# main.net
KiCad netlist of a schematic drawn in Altium Designer
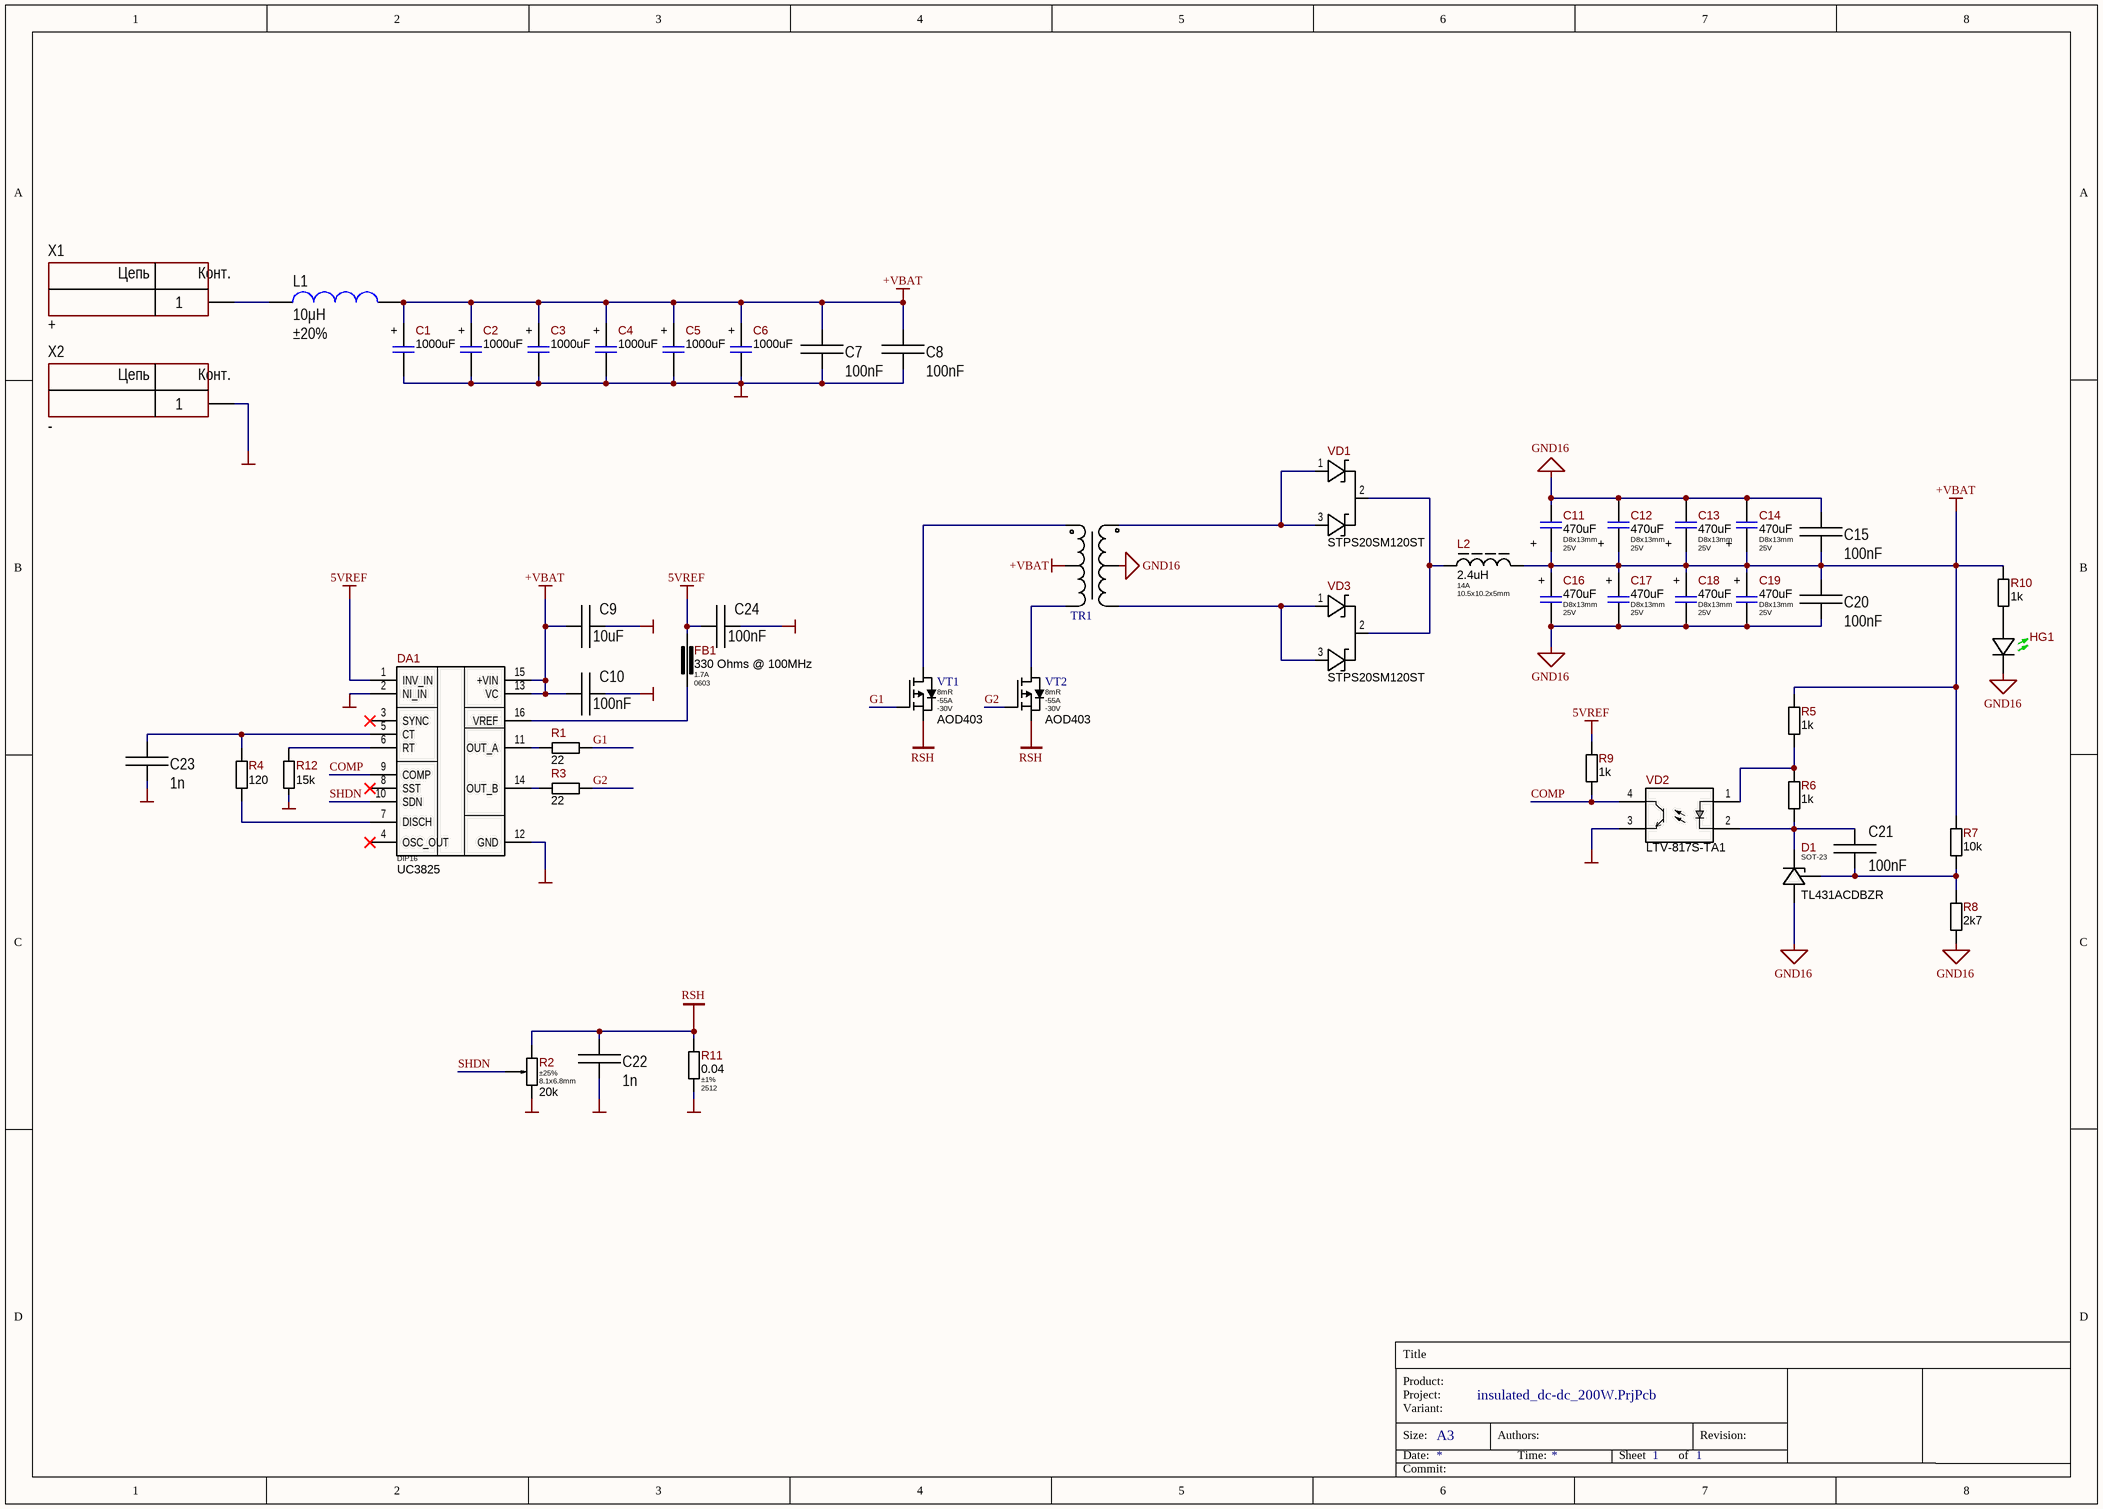
[diagram p0: main.SchDoc]

(export (version "E")
  (design (tool "Eeschema 10.0.6"))
  (components
    (comp (ref "C1")
      (value "1000uF")
      (footprint "CAP-AE-PTH-100D05x200H20")
      (description "1000uF 25V ±20% Aluminum Electrolytic Capacitors Radial, 2000 Hrs @ 105°C, 740mA Ripple Current")
      (fields (field (name "VOLTAGE") "25V") (field (name "PART NUMBER") "ESH108M025AH4AA"))
      (libsource (lib "capacitors") (part "ESH108M025AH4AA"))
    )
    (comp (ref "C2")
      (value "1000uF")
      (footprint "CAP-AE-PTH-100D05x200H20")
      (description "1000uF 25V ±20% Aluminum Electrolytic Capacitors Radial, 2000 Hrs @ 105°C, 740mA Ripple Current")
      (fields (field (name "VOLTAGE") "25V") (field (name "PART NUMBER") "ESH108M025AH4AA"))
      (libsource (lib "capacitors") (part "ESH108M025AH4AA"))
    )
    (comp (ref "C3")
      (value "1000uF")
      (footprint "CAP-AE-PTH-100D05x200H20")
      (description "1000uF 25V ±20% Aluminum Electrolytic Capacitors Radial, 2000 Hrs @ 105°C, 740mA Ripple Current")
      (fields (field (name "VOLTAGE") "25V") (field (name "PART NUMBER") "ESH108M025AH4AA"))
      (libsource (lib "capacitors") (part "ESH108M025AH4AA"))
    )
    (comp (ref "C4")
      (value "1000uF")
      (footprint "CAP-AE-PTH-100D05x200H20")
      (description "1000uF 25V ±20% Aluminum Electrolytic Capacitors Radial, 2000 Hrs @ 105°C, 740mA Ripple Current")
      (fields (field (name "VOLTAGE") "25V") (field (name "PART NUMBER") "ESH108M025AH4AA"))
      (libsource (lib "capacitors") (part "ESH108M025AH4AA"))
    )
    (comp (ref "C5")
      (value "1000uF")
      (footprint "CAP-AE-PTH-100D05x200H20")
      (description "1000uF 25V ±20% Aluminum Electrolytic Capacitors Radial, 2000 Hrs @ 105°C, 740mA Ripple Current")
      (fields (field (name "VOLTAGE") "25V") (field (name "PART NUMBER") "ESH108M025AH4AA"))
      (libsource (lib "capacitors") (part "ESH108M025AH4AA"))
    )
    (comp (ref "C6")
      (value "1000uF")
      (footprint "CAP-AE-PTH-100D05x200H20")
      (description "1000uF 25V ±20% Aluminum Electrolytic Capacitors Radial, 2000 Hrs @ 105°C, 740mA Ripple Current")
      (fields (field (name "VOLTAGE") "25V") (field (name "PART NUMBER") "ESH108M025AH4AA"))
      (libsource (lib "capacitors") (part "ESH108M025AH4AA"))
    )
    (comp (ref "C7")
      (value "100nF")
      (footprint "CAP: MKS2 (W=2.50MM)")
      (fields
        (field (name "MANUFACTURER") "Epcos")
        (field (name "PARTNUMBER") "B32774D4106K000")
        (field (name "VALUEMANUFACTURERPARTNUMBER") "Film capacitor, 100nF, 450VDC, ±10%, 10.9mOhm, 31.5x15 mm, -40...+105°C")
      )
      (libsource (lib "capacitor") (part "Film"))
    )
    (comp (ref "C8")
      (value "100nF")
      (footprint "CAP: MKS2 (W=2.50MM)")
      (fields
        (field (name "MANUFACTURER") "Epcos")
        (field (name "PARTNUMBER") "B32774D4106K000")
        (field (name "VALUEMANUFACTURERPARTNUMBER") "Film capacitor, 100nF, 450VDC, ±10%, 10.9mOhm, 31.5x15 mm, -40...+105°C")
      )
      (libsource (lib "capacitor") (part "Film"))
    )
    (comp (ref "C9")
      (value "10uF")
      (footprint "CAP: MKS2 (W=2.50MM)")
      (fields
        (field (name "MANUFACTURER") "Epcos")
        (field (name "PARTNUMBER") "B32774D4106K000")
        (field (name "VALUEMANUFACTURERPARTNUMBER") "Film capacitor, 10uF, 450VDC, ±10%, 10.9mOhm, 31.5x15 mm, -40...+105°C")
      )
      (libsource (lib "capacitor") (part "Film"))
    )
    (comp (ref "C10")
      (value "100nF")
      (footprint "CAP: MKS2 (W=2.50MM)")
      (fields
        (field (name "MANUFACTURER") "Epcos")
        (field (name "PARTNUMBER") "B32774D4106K000")
        (field (name "VALUEMANUFACTURERPARTNUMBER") "Film capacitor, 100nF, 450VDC, ±10%, 10.9mOhm, 31.5x15 mm, -40...+105°C")
      )
      (libsource (lib "capacitor") (part "Film"))
    )
    (comp (ref "C11")
      (value "470uF")
      (footprint "CAP-AE-PTH-80D05x130H15")
      (fields
        (field (name "PACKAGE") "D8x13mm")
        (field (name "VOLTAGE") "25V")
        (field (name "PART NUMBER") "KS-025V471MF130")
        (field (name "MANUFACTURER") "Koshin")
        (field (name "TOLERANCE") "±20%")
      )
      (libsource (lib "capacitors") (part "KS-025V471MF130"))
    )
    (comp (ref "C12")
      (value "470uF")
      (footprint "CAP-AE-PTH-80D05x130H15")
      (fields
        (field (name "PACKAGE") "D8x13mm")
        (field (name "VOLTAGE") "25V")
        (field (name "PART NUMBER") "KS-025V471MF130")
        (field (name "MANUFACTURER") "Koshin")
        (field (name "TOLERANCE") "±20%")
      )
      (libsource (lib "capacitors") (part "KS-025V471MF130"))
    )
    (comp (ref "C13")
      (value "470uF")
      (footprint "CAP-AE-PTH-80D05x130H15")
      (fields
        (field (name "PACKAGE") "D8x13mm")
        (field (name "VOLTAGE") "25V")
        (field (name "PART NUMBER") "KS-025V471MF130")
        (field (name "MANUFACTURER") "Koshin")
        (field (name "TOLERANCE") "±20%")
      )
      (libsource (lib "capacitors") (part "KS-025V471MF130"))
    )
    (comp (ref "C14")
      (value "470uF")
      (footprint "CAP-AE-PTH-80D05x130H15")
      (fields
        (field (name "PACKAGE") "D8x13mm")
        (field (name "VOLTAGE") "25V")
        (field (name "PART NUMBER") "KS-025V471MF130")
        (field (name "MANUFACTURER") "Koshin")
        (field (name "TOLERANCE") "±20%")
      )
      (libsource (lib "capacitors") (part "KS-025V471MF130"))
    )
    (comp (ref "C15")
      (value "100nF")
      (footprint "CAP: MKS2 (W=2.50MM)")
      (fields
        (field (name "MANUFACTURER") "Epcos")
        (field (name "PARTNUMBER") "B32774D4106K000")
        (field (name "VALUEMANUFACTURERPARTNUMBER") "Film capacitor, 100nF, 450VDC, ±10%, 10.9mOhm, 31.5x15 mm, -40...+105°C")
      )
      (libsource (lib "capacitor") (part "Film"))
    )
    (comp (ref "C16")
      (value "470uF")
      (footprint "CAP-AE-PTH-80D05x130H15")
      (fields
        (field (name "PACKAGE") "D8x13mm")
        (field (name "VOLTAGE") "25V")
        (field (name "PART NUMBER") "KS-025V471MF130")
        (field (name "MANUFACTURER") "Koshin")
        (field (name "TOLERANCE") "±20%")
      )
      (libsource (lib "capacitors") (part "KS-025V471MF130"))
    )
    (comp (ref "C17")
      (value "470uF")
      (footprint "CAP-AE-PTH-80D05x130H15")
      (fields
        (field (name "PACKAGE") "D8x13mm")
        (field (name "VOLTAGE") "25V")
        (field (name "PART NUMBER") "KS-025V471MF130")
        (field (name "MANUFACTURER") "Koshin")
        (field (name "TOLERANCE") "±20%")
      )
      (libsource (lib "capacitors") (part "KS-025V471MF130"))
    )
    (comp (ref "C18")
      (value "470uF")
      (footprint "CAP-AE-PTH-80D05x130H15")
      (fields
        (field (name "PACKAGE") "D8x13mm")
        (field (name "VOLTAGE") "25V")
        (field (name "PART NUMBER") "KS-025V471MF130")
        (field (name "MANUFACTURER") "Koshin")
        (field (name "TOLERANCE") "±20%")
      )
      (libsource (lib "capacitors") (part "KS-025V471MF130"))
    )
    (comp (ref "C19")
      (value "470uF")
      (footprint "CAP-AE-PTH-80D05x130H15")
      (fields
        (field (name "PACKAGE") "D8x13mm")
        (field (name "VOLTAGE") "25V")
        (field (name "PART NUMBER") "KS-025V471MF130")
        (field (name "MANUFACTURER") "Koshin")
        (field (name "TOLERANCE") "±20%")
      )
      (libsource (lib "capacitors") (part "KS-025V471MF130"))
    )
    (comp (ref "C20")
      (value "100nF")
      (footprint "CAP: MKS2 (W=2.50MM)")
      (fields
        (field (name "MANUFACTURER") "Epcos")
        (field (name "PARTNUMBER") "B32774D4106K000")
        (field (name "VALUEMANUFACTURERPARTNUMBER") "Film capacitor, 100nF, 450VDC, ±10%, 10.9mOhm, 31.5x15 mm, -40...+105°C")
      )
      (libsource (lib "capacitor") (part "Film"))
    )
    (comp (ref "C21")
      (value "100nF")
      (footprint "CAP: MKS2 (W=2.50MM)")
      (fields
        (field (name "MANUFACTURER") "Epcos")
        (field (name "PARTNUMBER") "B32774D4106K000")
        (field (name "VALUEMANUFACTURERPARTNUMBER") "Film capacitor, 100nF, 450VDC, ±10%, 10.9mOhm, 31.5x15 mm, -40...+105°C")
      )
      (libsource (lib "capacitor") (part "Film"))
    )
    (comp (ref "C22")
      (value "1n")
      (footprint "CAP: MKS2 (W=2.50MM)")
      (fields
        (field (name "MANUFACTURER") "Epcos")
        (field (name "PARTNUMBER") "B32774D4106K000")
        (field (name "VALUEMANUFACTURERPARTNUMBER") "Film capacitor, 1n, 450VDC, ±10%, 10.9mOhm, 31.5x15 mm, -40...+105°C")
      )
      (libsource (lib "capacitor") (part "Film"))
    )
    (comp (ref "C23")
      (value "1n")
      (footprint "CAP: MKS2 (W=2.50MM)")
      (fields
        (field (name "MANUFACTURER") "Epcos")
        (field (name "PARTNUMBER") "B32774D4106K000")
        (field (name "VALUEMANUFACTURERPARTNUMBER") "Film capacitor, 1n, 450VDC, ±10%, 10.9mOhm, 31.5x15 mm, -40...+105°C")
      )
      (libsource (lib "capacitor") (part "Film"))
    )
    (comp (ref "C24")
      (value "100nF")
      (footprint "CAP: MKS2 (W=2.50MM)")
      (fields
        (field (name "MANUFACTURER") "Epcos")
        (field (name "PARTNUMBER") "B32774D4106K000")
        (field (name "VALUEMANUFACTURERPARTNUMBER") "Film capacitor, 100nF, 450VDC, ±10%, 10.9mOhm, 31.5x15 mm, -40...+105°C")
      )
      (libsource (lib "capacitor") (part "Film"))
    )
    (comp (ref "D1")
      (value "TL431ACDBZR")
      (footprint "SOT-23_MED")
      (description "Adjustable Precision Shunt Regulator, Accuracy 1%,  SOT-23-3")
      (fields
        (field (name "PACKAGE") "SOT-23")
        (field (name "PART NUMBER") "TL431ACDBZR")
        (field (name "MANUFACTURER") "Texas Instruments")
      )
      (libsource (lib "ic") (part "TL431ACDBZR"))
    )
    (comp (ref "DA1")
      (value "UC3525")
      (footprint "DIP16")
      (fields
        (field (name "MANUFACTURER") "Texas")
        (field (name "PACKAGE") "DIP16")
        (field (name "PART NUMBER") "UC3825")
      )
      (libsource (lib "vitech_lib") (part "UC3525"))
    )
    (comp (ref "FB1")
      (value "330 Ohms @ 100MHz")
      (footprint "BLM18-Series_H80T15")
      (description "330 Ohms @ 100 MHz Power Line Ferrite Bead 0603, 1.7A 80mOhm")
      (fields
        (field (name "CURRENT") "1.7A")
        (field (name "PACKAGE") "0603")
        (field (name "PART NUMBER") "BLM18KG331SH1D")
        (field (name "TOLERANCE") "±25%")
      )
      (libsource (lib "inductors") (part "BLM18KG331SH1D"))
    )
    (comp (ref "HG1")
      (value "LTST-C171GKT")
      (footprint "LTST-C171GKT")
      (description "Low Power LED, Green 565nm, Clear, SMD 0805, Vf 2.1V - 2.6V, 5 ~ 12mcd @ 20 mA, 130°")
      (fields (field (name "MANUFACTURER") "Lite-On Optoelectronics"))
      (libsource (lib "opto") (part "LTST-C171GKT"))
    )
    (comp (ref "L1")
      (value "10μH")
      (footprint "IND: R22.9/14/7.62 (H)")
      (fields
        (field (name "MANUFACTURER") "Magnetics")
        (field (name "PARTNUMBER") "0077310A7")
        (field (name "VALUEMANUFACTURERPARTNUMBER") "Fixed inductor, 10μH, ±20%, R22.9/14/7.62, Kool Mu, µ=125, 90 нГн/витков2")
        (field (name "TOLERANCE") "±20%")
      )
      (libsource (lib "inductor") (part "Inductor_R22.9/14/7.62"))
    )
    (comp (ref "L2")
      (value "2.4uH")
      (footprint "744325240")
      (description "2.4uH Shielded Wirewound Inductor 14A 4.75mOhm Max, 10.5x10.2mm, Height 5mm Max")
      (fields
        (field (name "CURRENT") "14A")
        (field (name "PACKAGE") "10.5x10.2x5mm")
        (field (name "PART NUMBER") "744325240")
        (field (name "TOLERANCE") "±20%")
      )
      (libsource (lib "inductors") (part "744325240"))
    )
    (comp (ref "R1")
      (value "22")
      (footprint "R_ANY_CHIP_0805_MED")
      (description "22 Ohms ±5%, 1/8W 0805 Thick Film Resistor")
      (fields (field (name "TOLERANCE") "±5%") (field (name "PART NUMBER") "RC0805JR-0722RL"))
      (libsource (lib "resistors") (part "RC0805JR-0722RL"))
    )
    (comp (ref "R2")
      (value "20k")
      (footprint "3306F-1-xxx")
      (description "20 kOhms ±25%, 0.2W, PTH Trimmer Potentiometer, Cermet, Turn Top Adjustment")
      (fields
        (field (name "TOLERANCE") "±25%")
        (field (name "PACKAGE") "8.1x6.8mm")
        (field (name "PART NUMBER") "3306F-1-203")
        (field (name "MANUFACTURER") "Bourns")
      )
      (libsource (lib "resistors") (part "3306F-1-203"))
    )
    (comp (ref "R3")
      (value "22")
      (footprint "R_ANY_CHIP_0805_MED")
      (description "22 Ohms ±5%, 1/8W 0805 Thick Film Resistor")
      (fields (field (name "TOLERANCE") "±5%") (field (name "PART NUMBER") "RC0805JR-0722RL"))
      (libsource (lib "resistors") (part "RC0805JR-0722RL"))
    )
    (comp (ref "R4")
      (value "120")
      (footprint "R_ANY_CHIP_0805_MED")
      (description "22 Ohms ±5%, 1/8W 0805 Thick Film Resistor")
      (fields (field (name "TOLERANCE") "±5%") (field (name "PART NUMBER") "RC0805JR-0722RL"))
      (libsource (lib "resistors") (part "RC0805JR-0722RL"))
    )
    (comp (ref "R5")
      (value "1k")
      (footprint "R_ANY_CHIP_0805_MED")
      (description "22 Ohms ±5%, 1/8W 0805 Thick Film Resistor")
      (fields (field (name "TOLERANCE") "±5%") (field (name "PART NUMBER") "RC0805JR-0722RL"))
      (libsource (lib "resistors") (part "RC0805JR-0722RL"))
    )
    (comp (ref "R6")
      (value "1k")
      (footprint "R_ANY_CHIP_0805_MED")
      (description "22 Ohms ±5%, 1/8W 0805 Thick Film Resistor")
      (fields (field (name "TOLERANCE") "±5%") (field (name "PART NUMBER") "RC0805JR-0722RL"))
      (libsource (lib "resistors") (part "RC0805JR-0722RL"))
    )
    (comp (ref "R7")
      (value "10k")
      (footprint "R_ANY_CHIP_0805_MED")
      (description "22 Ohms ±5%, 1/8W 0805 Thick Film Resistor")
      (fields (field (name "TOLERANCE") "±5%") (field (name "PART NUMBER") "RC0805JR-0722RL"))
      (libsource (lib "resistors") (part "RC0805JR-0722RL"))
    )
    (comp (ref "R8")
      (value "2k7")
      (footprint "R_ANY_CHIP_0805_MED")
      (description "22 Ohms ±5%, 1/8W 0805 Thick Film Resistor")
      (fields (field (name "TOLERANCE") "±5%") (field (name "PART NUMBER") "RC0805JR-0722RL"))
      (libsource (lib "resistors") (part "RC0805JR-0722RL"))
    )
    (comp (ref "R9")
      (value "1k")
      (footprint "R_ANY_CHIP_0805_MED")
      (description "22 Ohms ±5%, 1/8W 0805 Thick Film Resistor")
      (fields (field (name "TOLERANCE") "±5%") (field (name "PART NUMBER") "RC0805JR-0722RL"))
      (libsource (lib "resistors") (part "RC0805JR-0722RL"))
    )
    (comp (ref "R10")
      (value "1k")
      (footprint "R_ANY_CHIP_0805_MED")
      (description "22 Ohms ±5%, 1/8W 0805 Thick Film Resistor")
      (fields (field (name "TOLERANCE") "±5%") (field (name "PART NUMBER") "RC0805JR-0722RL"))
      (libsource (lib "resistors") (part "RC0805JR-0722RL"))
    )
    (comp (ref "R11")
      (value "0.04")
      (footprint "HoLLR2512-Series")
      (description "40mOhm ±1%, 2W Surface Mount 77.5A ±50ppm 2512 Encapsulated Metal Alloy Current Sense Resistors")
      (fields
        (field (name "TOLERANCE") "±1%")
        (field (name "PACKAGE") "2512")
        (field (name "PART NUMBER") "HoLLR2512-2W-40mR-1%")
        (field (name "MANUFACTURER") "Milliohm")
      )
      (libsource (lib "resistors") (part "HoLLR2512-2W-40mR-1%"))
    )
    (comp (ref "R12")
      (value "15k")
      (footprint "R_ANY_CHIP_0805_MED")
      (description "22 Ohms ±5%, 1/8W 0805 Thick Film Resistor")
      (fields (field (name "TOLERANCE") "±5%") (field (name "PART NUMBER") "RC0805JR-0722RL"))
      (libsource (lib "resistors") (part "RC0805JR-0722RL"))
    )
    (comp (ref "TR1")
      (value "TR")
      (footprint "TR: R32.8/20.1/10.7 (L) - MidPoint - 2")
      (fields
        (field (name "MANUFACTURER") "Handmade")
        (field (name "PART NUMBER") "RLB0914-3R3ML-ND")
        (field (name "TOLERANCE") "±20%")
      )
      (libsource (lib "vitech_lib") (part "Toroidal Transformator Midpoint_1"))
    )
    (comp (ref "VD1")
      (value "DIODE SCHOTTKY")
      (footprint "TO220(H)")
      (description "Diode Schottky Array 1 Pair Common Cathode, 120V 20A, TO-220")
      (fields
        (field (name "VOLTAGE") "120V")
        (field (name "MANUFACTURER") "STMicroelectronics")
        (field (name "PART NUMBER") "STPS20SM120ST")
      )
      (libsource (lib "vitech_lib") (part "DIODE SCHOTTKY"))
    )
    (comp (ref "VD2")
      (value "LTV-817S-TA1")
      (footprint "LTV-817S-TA1_REC")
      (description "1-Channel Photocoupler, 5kV, SSOP-4")
      (fields
        (field (name "PART NUMBER") "LTV-817S-TA1")
        (field (name "MANUFACTURER") "Lite-On Optoelectronics")
      )
      (libsource (lib "opto") (part "LTV-817S-TA1"))
    )
    (comp (ref "VD3")
      (value "DIODE SCHOTTKY")
      (footprint "TO220(H)")
      (description "Diode Schottky Array 1 Pair Common Cathode, 120V 20A, TO-220")
      (fields
        (field (name "VOLTAGE") "120V")
        (field (name "MANUFACTURER") "STMicroelectronics")
        (field (name "PART NUMBER") "STPS20SM120ST")
      )
      (libsource (lib "vitech_lib") (part "DIODE SCHOTTKY"))
    )
    (comp (ref "VT1")
      (value "AOD403")
      (footprint "TO220(H)")
      (description "P-MOSFET; полевой; -30В; -55А; 45Вт; TO252")
      (fields
        (field (name "RDS") "8mR")
        (field (name "ID") "-55А")
        (field (name "VDS") "-30V")
        (field (name "PART NUMBER") "AOD403")
      )
      (libsource (lib "vitech_lib") (part "N-CH_MOSFET"))
    )
    (comp (ref "VT2")
      (value "AOD403")
      (footprint "TO220(H)")
      (description "P-MOSFET; полевой; -30В; -55А; 45Вт; TO252")
      (fields
        (field (name "RDS") "8mR")
        (field (name "ID") "-55А")
        (field (name "VDS") "-30V")
        (field (name "PART NUMBER") "AOD403")
      )
      (libsource (lib "vitech_lib") (part "N-CH_MOSFET"))
    )
    (comp (ref "X1")
      (value "~")
      (footprint "CON: 8191")
      (fields
        (field (name "VALUEMANUFACTURERPARTNUMBER") "Power connector, *, *")
        (field (name "COMMENTTEXT") "+")
      )
      (libsource (lib "connector") (part "Connector_single_power"))
    )
    (comp (ref "X2")
      (value "~")
      (footprint "CON: 8191")
      (fields
        (field (name "VALUEMANUFACTURERPARTNUMBER") "Power connector, *, *")
        (field (name "COMMENTTEXT") "-")
      )
      (libsource (lib "connector") (part "Connector_single_power"))
    )
  )
  (nets
    (net (code "1") (name "+VBAT") (class "Default")
      (node (ref "C1") (pin "1") (pinfunction "1_1") (pintype "passive"))
      (node (ref "C10") (pin "1") (pinfunction "1_1") (pintype "passive"))
      (node (ref "C11") (pin "1") (pinfunction "1_1") (pintype "passive"))
      (node (ref "C12") (pin "1") (pinfunction "1_1") (pintype "passive"))
      (node (ref "C13") (pin "1") (pinfunction "1_1") (pintype "passive"))
      (node (ref "C14") (pin "1") (pinfunction "1_1") (pintype "passive"))
      (node (ref "C16") (pin "1") (pinfunction "1_1") (pintype "passive"))
      (node (ref "C17") (pin "1") (pinfunction "1_1") (pintype "passive"))
      (node (ref "C18") (pin "1") (pinfunction "1_1") (pintype "passive"))
      (node (ref "C19") (pin "1") (pinfunction "1_1") (pintype "passive"))
      (node (ref "C2") (pin "1") (pinfunction "1_1") (pintype "passive"))
      (node (ref "C20") (pin "1") (pinfunction "1_1") (pintype "passive"))
      (node (ref "C3") (pin "1") (pinfunction "1_1") (pintype "passive"))
      (node (ref "C4") (pin "1") (pinfunction "1_1") (pintype "passive"))
      (node (ref "C5") (pin "1") (pinfunction "1_1") (pintype "passive"))
      (node (ref "C6") (pin "1") (pinfunction "1_1") (pintype "passive"))
      (node (ref "C7") (pin "1") (pinfunction "1_1") (pintype "passive"))
      (node (ref "C8") (pin "1") (pinfunction "1_1") (pintype "passive"))
      (node (ref "C9") (pin "1") (pinfunction "1_1") (pintype "passive"))
      (node (ref "DA1") (pin "13") (pinfunction "VC_13") (pintype "passive"))
      (node (ref "DA1") (pin "15") (pinfunction "+VIN_15") (pintype "passive"))
      (node (ref "L1") (pin "1") (pinfunction "1_1") (pintype "passive"))
      (node (ref "L2") (pin "2") (pintype "passive"))
      (node (ref "R10") (pin "2") (pintype "passive"))
      (node (ref "R5") (pin "2") (pintype "passive"))
      (node (ref "R7") (pin "2") (pintype "passive"))
      (node (ref "TR1") (pin "3") (pintype "passive"))
    )
    (net (code "2") (name "/COMP") (class "Default")
      (node (ref "DA1") (pin "9") (pinfunction "COMP_9") (pintype "passive"))
      (node (ref "R9") (pin "1") (pintype "passive"))
      (node (ref "VD2") (pin "4") (pinfunction "Collector_4") (pintype "passive"))
    )
    (net (code "3") (name "/G1") (class "Default")
      (node (ref "R1") (pin "2") (pintype "passive"))
      (node (ref "VT1") (pin "1") (pinfunction "G_1") (pintype "passive"))
    )
    (net (code "4") (name "/G2") (class "Default")
      (node (ref "R3") (pin "2") (pintype "passive"))
      (node (ref "VT2") (pin "1") (pinfunction "G_1") (pintype "passive"))
    )
    (net (code "5") (name "/SHDN") (class "Default")
      (node (ref "DA1") (pin "10") (pinfunction "SDN_10") (pintype "passive"))
      (node (ref "R2") (pin "2") (pinfunction "WIPER_2") (pintype "passive"))
    )
    (net (code "6") (name "5VREF") (class "Default")
      (node (ref "C24") (pin "1") (pinfunction "1_1") (pintype "passive"))
      (node (ref "DA1") (pin "1") (pinfunction "INV_IN_1") (pintype "passive"))
      (node (ref "FB1") (pin "2") (pintype "passive"))
      (node (ref "R9") (pin "2") (pintype "passive"))
    )
    (net (code "7") (name "GND") (class "Default")
      (node (ref "C1") (pin "2") (pinfunction "2_2") (pintype "passive"))
      (node (ref "C10") (pin "2") (pinfunction "2_2") (pintype "passive"))
      (node (ref "C2") (pin "2") (pinfunction "2_2") (pintype "passive"))
      (node (ref "C22") (pin "1") (pinfunction "1_1") (pintype "passive"))
      (node (ref "C23") (pin "2") (pinfunction "2_2") (pintype "passive"))
      (node (ref "C24") (pin "2") (pinfunction "2_2") (pintype "passive"))
      (node (ref "C3") (pin "2") (pinfunction "2_2") (pintype "passive"))
      (node (ref "C4") (pin "2") (pinfunction "2_2") (pintype "passive"))
      (node (ref "C5") (pin "2") (pinfunction "2_2") (pintype "passive"))
      (node (ref "C6") (pin "2") (pinfunction "2_2") (pintype "passive"))
      (node (ref "C7") (pin "2") (pinfunction "2_2") (pintype "passive"))
      (node (ref "C9") (pin "2") (pinfunction "2_2") (pintype "passive"))
      (node (ref "DA1") (pin "12") (pinfunction "GND_12") (pintype "passive"))
      (node (ref "DA1") (pin "2") (pinfunction "NI_IN_2") (pintype "passive"))
      (node (ref "R11") (pin "2") (pintype "passive"))
      (node (ref "R12") (pin "1") (pintype "passive"))
      (node (ref "R2") (pin "1") (pinfunction "CCW_1") (pintype "passive"))
      (node (ref "VD2") (pin "3") (pinfunction "Emitter_3") (pintype "passive"))
      (node (ref "X2") (pin "1") (pinfunction "1_1") (pintype "passive"))
    )
    (net (code "8") (name "GND16") (class "Default")
      (node (ref "C11") (pin "2") (pinfunction "2_2") (pintype "passive"))
      (node (ref "C12") (pin "2") (pinfunction "2_2") (pintype "passive"))
      (node (ref "C13") (pin "2") (pinfunction "2_2") (pintype "passive"))
      (node (ref "C14") (pin "2") (pinfunction "2_2") (pintype "passive"))
      (node (ref "C15") (pin "1") (pinfunction "1_1") (pintype "passive"))
      (node (ref "C16") (pin "2") (pinfunction "2_2") (pintype "passive"))
      (node (ref "C17") (pin "2") (pinfunction "2_2") (pintype "passive"))
      (node (ref "C18") (pin "2") (pinfunction "2_2") (pintype "passive"))
      (node (ref "C19") (pin "2") (pinfunction "2_2") (pintype "passive"))
      (node (ref "C20") (pin "2") (pinfunction "2_2") (pintype "passive"))
      (node (ref "D1") (pin "3") (pinfunction "A_3") (pintype "passive"))
      (node (ref "HG1") (pin "CA") (pinfunction "Cathode_CA") (pintype "passive"))
      (node (ref "R8") (pin "1") (pintype "passive"))
      (node (ref "TR1") (pin "6") (pintype "passive"))
    )
    (net (code "9") (name "Net-(D1-C)") (class "Default")
      (node (ref "C21") (pin "1") (pinfunction "1_1") (pintype "passive"))
      (node (ref "D1") (pin "1") (pinfunction "C_1") (pintype "passive"))
      (node (ref "R6") (pin "1") (pintype "passive"))
      (node (ref "VD2") (pin "2") (pinfunction "Cathode_2") (pintype "passive"))
    )
    (net (code "10") (name "Net-(D1-REF)") (class "Default")
      (node (ref "C21") (pin "2") (pinfunction "2_2") (pintype "passive"))
      (node (ref "D1") (pin "2") (pinfunction "REF_2") (pintype "passive"))
      (node (ref "R7") (pin "1") (pintype "passive"))
      (node (ref "R8") (pin "2") (pintype "passive"))
    )
    (net (code "11") (name "Net-(DA1-CT)") (class "Default")
      (node (ref "C23") (pin "1") (pinfunction "1_1") (pintype "passive"))
      (node (ref "DA1") (pin "5") (pinfunction "CT_5") (pintype "passive"))
      (node (ref "R4") (pin "2") (pintype "passive"))
    )
    (net (code "12") (name "Net-(DA1-DISCH)") (class "Default")
      (node (ref "DA1") (pin "7") (pinfunction "DISCH_7") (pintype "passive"))
      (node (ref "R4") (pin "1") (pintype "passive"))
    )
    (net (code "13") (name "Net-(DA1-OUT_A)") (class "Default")
      (node (ref "DA1") (pin "11") (pinfunction "OUT_A_11") (pintype "passive"))
      (node (ref "R1") (pin "1") (pintype "passive"))
    )
    (net (code "14") (name "Net-(DA1-OUT_B)") (class "Default")
      (node (ref "DA1") (pin "14") (pinfunction "OUT_B_14") (pintype "passive"))
      (node (ref "R3") (pin "1") (pintype "passive"))
    )
    (net (code "15") (name "Net-(DA1-RT)") (class "Default")
      (node (ref "DA1") (pin "6") (pinfunction "RT_6") (pintype "passive"))
      (node (ref "R12") (pin "2") (pintype "passive"))
    )
    (net (code "16") (name "Net-(DA1-VREF)") (class "Default")
      (node (ref "DA1") (pin "16") (pinfunction "VREF_16") (pintype "passive"))
      (node (ref "FB1") (pin "1") (pintype "passive"))
    )
    (net (code "17") (name "Net-(HG1-Anode)") (class "Default")
      (node (ref "HG1") (pin "AN") (pinfunction "Anode_AN") (pintype "passive"))
      (node (ref "R10") (pin "1") (pintype "passive"))
    )
    (net (code "18") (name "Net-(L1-Pad2)") (class "Default")
      (node (ref "L1") (pin "2") (pinfunction "2_2") (pintype "passive"))
      (node (ref "X1") (pin "1") (pinfunction "1_1") (pintype "passive"))
    )
    (net (code "19") (name "Net-(VD1-Anode_1)") (class "Default")
      (node (ref "TR1") (pin "4") (pintype "passive"))
      (node (ref "VD1") (pin "1") (pinfunction "Anode_1_1") (pintype "passive"))
      (node (ref "VD1") (pin "3") (pinfunction "Anode_2_3") (pintype "passive"))
    )
    (net (code "20") (name "Net-(VD1-Cathode)") (class "Default")
      (node (ref "L2") (pin "1") (pintype "passive"))
      (node (ref "VD1") (pin "2") (pinfunction "Cathode_2") (pintype "passive"))
      (node (ref "VD3") (pin "2") (pinfunction "Cathode_2") (pintype "passive"))
    )
    (net (code "21") (name "Net-(VD2-Anode)") (class "Default")
      (node (ref "R5") (pin "1") (pintype "passive"))
      (node (ref "R6") (pin "2") (pintype "passive"))
      (node (ref "VD2") (pin "1") (pinfunction "Anode_1") (pintype "passive"))
    )
    (net (code "22") (name "Net-(VD3-Anode_1)") (class "Default")
      (node (ref "TR1") (pin "5") (pintype "passive"))
      (node (ref "VD3") (pin "1") (pinfunction "Anode_1_1") (pintype "passive"))
      (node (ref "VD3") (pin "3") (pinfunction "Anode_2_3") (pintype "passive"))
    )
    (net (code "23") (name "Net-(VT1-D)") (class "Default")
      (node (ref "TR1") (pin "1") (pintype "passive"))
      (node (ref "VT1") (pin "2") (pinfunction "D_2") (pintype "passive"))
    )
    (net (code "24") (name "Net-(VT2-D)") (class "Default")
      (node (ref "TR1") (pin "2") (pintype "passive"))
      (node (ref "VT2") (pin "2") (pinfunction "D_2") (pintype "passive"))
    )
    (net (code "25") (name "RSH") (class "Default")
      (node (ref "C22") (pin "2") (pinfunction "2_2") (pintype "passive"))
      (node (ref "R11") (pin "1") (pintype "passive"))
      (node (ref "R2") (pin "3") (pinfunction "CW_3") (pintype "passive"))
      (node (ref "VT1") (pin "3") (pinfunction "S_3") (pintype "passive"))
      (node (ref "VT2") (pin "3") (pinfunction "S_3") (pintype "passive"))
    )
    (net (code "26") (name "unconnected-(C8-Pad2)") (class "Default")
      (node (ref "C8") (pin "2") (pinfunction "2_2") (pintype "passive"))
    )
    (net (code "27") (name "unconnected-(C15-Pad2)") (class "Default")
      (node (ref "C15") (pin "2") (pinfunction "2_2") (pintype "passive"))
    )
    (net (code "28") (name "unconnected-(DA1-OSC_OUT-Pad4)") (class "Default")
      (node (ref "DA1") (pin "4") (pinfunction "OSC_OUT_4") (pintype "passive+no_connect"))
    )
    (net (code "29") (name "unconnected-(DA1-SST-Pad8)") (class "Default")
      (node (ref "DA1") (pin "8") (pinfunction "SST_8") (pintype "passive+no_connect"))
    )
    (net (code "30") (name "unconnected-(DA1-SYNC-Pad3)") (class "Default")
      (node (ref "DA1") (pin "3") (pinfunction "SYNC_3") (pintype "passive+no_connect"))
    )
  )
)
